# Clape_SCH.net
KiCad netlist of a schematic drawn in Altium Designer
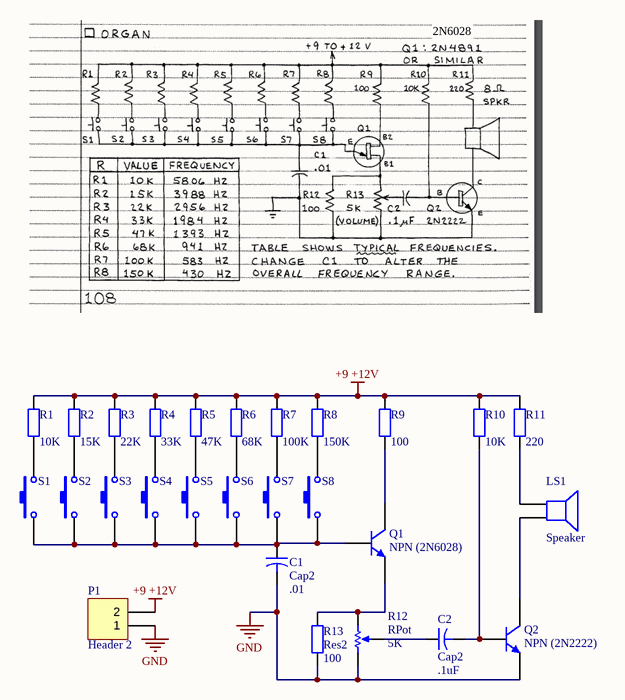
[diagram p0: Clape SCH.SchDoc]

(export (version "E")
  (design (tool "Eeschema 10.0.6"))
  (components
    (comp (ref "C1")
      (value "Cap2")
      (footprint "CAPR5-4X5")
      (description "Capacitor")
      (fields (field (name "ALTIUM_VALUE") ".01") (field (name "PUBLISHER") "Altium Limited"))
      (libsource (lib "Miscellaneous Devices") (part "Cap2"))
    )
    (comp (ref "C2")
      (value "Cap2")
      (footprint "CAPR5-4X5")
      (description "Capacitor")
      (fields (field (name "ALTIUM_VALUE") ".1uF") (field (name "PUBLISHER") "Altium Limited"))
      (libsource (lib "Miscellaneous Devices") (part "Cap2"))
    )
    (comp (ref "LS1")
      (value "Speaker")
      (footprint "PIN2")
      (description "Loudspeaker")
      (fields (field (name "PUBLISHER") "Altium Limited"))
      (libsource (lib "Miscellaneous Devices") (part "Speaker"))
    )
    (comp (ref "P1")
      (value "Header 2")
      (footprint "HDR1X2")
      (description "Header, 2-Pin")
      (fields (field (name "PUBLISHER") "Altium Limited"))
      (libsource (lib "Miscellaneous Connectors") (part "Header 2"))
    )
    (comp (ref "Q1")
      (value "NPN (2N6028)")
      (footprint "TO-226-AA")
      (description "NPN Bipolar Transistor")
      (fields (field (name "PUBLISHER") "Altium Limited"))
      (libsource (lib "Miscellaneous Devices") (part "NPN"))
    )
    (comp (ref "Q2")
      (value "NPN (2N2222)")
      (footprint "TO-226-AA")
      (description "NPN Bipolar Transistor")
      (fields (field (name "PUBLISHER") "Altium Limited"))
      (libsource (lib "Miscellaneous Devices") (part "NPN"))
    )
    (comp (ref "R1")
      (value "10K")
      (footprint "AXIAL-0.4")
      (description "Resistor")
      (fields (field (name "Comment") "Res2") (field (name "PUBLISHER") "Altium Limited"))
      (libsource (lib "Miscellaneous Devices") (part "Res2"))
    )
    (comp (ref "R2")
      (value "15K")
      (footprint "AXIAL-0.4")
      (description "Resistor")
      (fields (field (name "Comment") "Res2") (field (name "PUBLISHER") "Altium Limited"))
      (libsource (lib "Miscellaneous Devices") (part "Res2"))
    )
    (comp (ref "R3")
      (value "22K")
      (footprint "AXIAL-0.4")
      (description "Resistor")
      (fields (field (name "Comment") "Res2") (field (name "PUBLISHER") "Altium Limited"))
      (libsource (lib "Miscellaneous Devices") (part "Res2"))
    )
    (comp (ref "R4")
      (value "33K")
      (footprint "AXIAL-0.4")
      (description "Resistor")
      (fields (field (name "Comment") "Res2") (field (name "PUBLISHER") "Altium Limited"))
      (libsource (lib "Miscellaneous Devices") (part "Res2"))
    )
    (comp (ref "R5")
      (value "47K")
      (footprint "AXIAL-0.4")
      (description "Resistor")
      (fields (field (name "Comment") "Res2") (field (name "PUBLISHER") "Altium Limited"))
      (libsource (lib "Miscellaneous Devices") (part "Res2"))
    )
    (comp (ref "R6")
      (value "68K")
      (footprint "AXIAL-0.4")
      (description "Resistor")
      (fields (field (name "Comment") "Res2") (field (name "PUBLISHER") "Altium Limited"))
      (libsource (lib "Miscellaneous Devices") (part "Res2"))
    )
    (comp (ref "R7")
      (value "100K")
      (footprint "AXIAL-0.4")
      (description "Resistor")
      (fields (field (name "Comment") "Res2") (field (name "PUBLISHER") "Altium Limited"))
      (libsource (lib "Miscellaneous Devices") (part "Res2"))
    )
    (comp (ref "R8")
      (value "150K")
      (footprint "AXIAL-0.4")
      (description "Resistor")
      (fields (field (name "Comment") "Res2") (field (name "PUBLISHER") "Altium Limited"))
      (libsource (lib "Miscellaneous Devices") (part "Res2"))
    )
    (comp (ref "R9")
      (value "100")
      (footprint "AXIAL-0.4")
      (description "Resistor")
      (fields (field (name "Comment") "Res2") (field (name "PUBLISHER") "Altium Limited"))
      (libsource (lib "Miscellaneous Devices") (part "Res2"))
    )
    (comp (ref "R10")
      (value "10K")
      (footprint "AXIAL-0.4")
      (description "Resistor")
      (fields (field (name "Comment") "Res2") (field (name "PUBLISHER") "Altium Limited"))
      (libsource (lib "Miscellaneous Devices") (part "Res2"))
    )
    (comp (ref "R11")
      (value "220")
      (footprint "AXIAL-0.4")
      (description "Resistor")
      (fields (field (name "Comment") "Res2") (field (name "PUBLISHER") "Altium Limited"))
      (libsource (lib "Miscellaneous Devices") (part "Res2"))
    )
    (comp (ref "R12")
      (value "RPot")
      (footprint "VR5")
      (description "Potentiometer")
      (fields (field (name "ALTIUM_VALUE") "5K") (field (name "PUBLISHER") "Altium Limited"))
      (libsource (lib "Miscellaneous Devices") (part "RPot"))
    )
    (comp (ref "R13")
      (value "Res2")
      (footprint "AXIAL-0.4")
      (description "Resistor")
      (fields (field (name "ALTIUM_VALUE") "100") (field (name "PUBLISHER") "Altium Limited"))
      (libsource (lib "Miscellaneous Devices") (part "Res2"))
    )
    (comp (ref "S1")
      (value "SW-PB")
      (footprint "SPST-2")
      (description "Switch")
      (fields (field (name "PUBLISHER") "Altium Limited"))
      (libsource (lib "Miscellaneous Devices") (part "SW-PB"))
    )
    (comp (ref "S2")
      (value "SW-PB")
      (footprint "SPST-2")
      (description "Switch")
      (fields (field (name "PUBLISHER") "Altium Limited"))
      (libsource (lib "Miscellaneous Devices") (part "SW-PB"))
    )
    (comp (ref "S3")
      (value "SW-PB")
      (footprint "SPST-2")
      (description "Switch")
      (fields (field (name "PUBLISHER") "Altium Limited"))
      (libsource (lib "Miscellaneous Devices") (part "SW-PB"))
    )
    (comp (ref "S4")
      (value "SW-PB")
      (footprint "SPST-2")
      (description "Switch")
      (fields (field (name "PUBLISHER") "Altium Limited"))
      (libsource (lib "Miscellaneous Devices") (part "SW-PB"))
    )
    (comp (ref "S5")
      (value "SW-PB")
      (footprint "SPST-2")
      (description "Switch")
      (fields (field (name "PUBLISHER") "Altium Limited"))
      (libsource (lib "Miscellaneous Devices") (part "SW-PB"))
    )
    (comp (ref "S6")
      (value "SW-PB")
      (footprint "SPST-2")
      (description "Switch")
      (fields (field (name "PUBLISHER") "Altium Limited"))
      (libsource (lib "Miscellaneous Devices") (part "SW-PB"))
    )
    (comp (ref "S7")
      (value "SW-PB")
      (footprint "SPST-2")
      (description "Switch")
      (fields (field (name "PUBLISHER") "Altium Limited"))
      (libsource (lib "Miscellaneous Devices") (part "SW-PB"))
    )
    (comp (ref "S8")
      (value "SW-PB")
      (footprint "SPST-2")
      (description "Switch")
      (fields (field (name "PUBLISHER") "Altium Limited"))
      (libsource (lib "Miscellaneous Devices") (part "SW-PB"))
    )
  )
  (nets
    (net (code "1") (name "+9 +12V") (class "Default")
      (node (ref "P1") (pin "2") (pinfunction "2_2") (pintype "passive"))
      (node (ref "R1") (pin "2") (pinfunction "2_2") (pintype "passive"))
      (node (ref "R10") (pin "2") (pinfunction "2_2") (pintype "passive"))
      (node (ref "R11") (pin "2") (pinfunction "2_2") (pintype "passive"))
      (node (ref "R2") (pin "2") (pinfunction "2_2") (pintype "passive"))
      (node (ref "R3") (pin "2") (pinfunction "2_2") (pintype "passive"))
      (node (ref "R4") (pin "2") (pinfunction "2_2") (pintype "passive"))
      (node (ref "R5") (pin "2") (pinfunction "2_2") (pintype "passive"))
      (node (ref "R6") (pin "2") (pinfunction "2_2") (pintype "passive"))
      (node (ref "R7") (pin "2") (pinfunction "2_2") (pintype "passive"))
      (node (ref "R8") (pin "2") (pinfunction "2_2") (pintype "passive"))
      (node (ref "R9") (pin "2") (pinfunction "2_2") (pintype "passive"))
    )
    (net (code "2") (name "GND") (class "Default")
      (node (ref "C1") (pin "2") (pinfunction "2_2") (pintype "passive"))
      (node (ref "P1") (pin "1") (pinfunction "1_1") (pintype "passive"))
      (node (ref "Q2") (pin "3") (pinfunction "E_3") (pintype "passive"))
      (node (ref "R12") (pin "1") (pinfunction "TOP_1") (pintype "passive"))
      (node (ref "R13") (pin "1") (pinfunction "1_1") (pintype "passive"))
    )
    (net (code "3") (name "Net-(LS1-Pad1)") (class "Default")
      (node (ref "LS1") (pin "1") (pinfunction "1_1") (pintype "passive"))
      (node (ref "R11") (pin "1") (pinfunction "1_1") (pintype "passive"))
    )
    (net (code "4") (name "Net-(Q1-B)") (class "Default")
      (node (ref "C1") (pin "1") (pinfunction "1_1") (pintype "passive"))
      (node (ref "Q1") (pin "2") (pinfunction "B_2") (pintype "passive"))
      (node (ref "S1") (pin "1") (pinfunction "1_1") (pintype "passive"))
      (node (ref "S2") (pin "1") (pinfunction "1_1") (pintype "passive"))
      (node (ref "S3") (pin "1") (pinfunction "1_1") (pintype "passive"))
      (node (ref "S4") (pin "1") (pinfunction "1_1") (pintype "passive"))
      (node (ref "S5") (pin "1") (pinfunction "1_1") (pintype "passive"))
      (node (ref "S6") (pin "1") (pinfunction "1_1") (pintype "passive"))
      (node (ref "S7") (pin "1") (pinfunction "1_1") (pintype "passive"))
      (node (ref "S8") (pin "1") (pinfunction "1_1") (pintype "passive"))
    )
    (net (code "5") (name "Net-(Q1-C)") (class "Default")
      (node (ref "Q1") (pin "1") (pinfunction "C_1") (pintype "passive"))
      (node (ref "R9") (pin "1") (pinfunction "1_1") (pintype "passive"))
    )
    (net (code "6") (name "Net-(Q1-E)") (class "Default")
      (node (ref "Q1") (pin "3") (pinfunction "E_3") (pintype "passive"))
      (node (ref "R12") (pin "2") (pinfunction "BOT_2") (pintype "passive"))
      (node (ref "R13") (pin "2") (pinfunction "2_2") (pintype "passive"))
    )
    (net (code "7") (name "Net-(Q2-B)") (class "Default")
      (node (ref "C2") (pin "2") (pinfunction "2_2") (pintype "passive"))
      (node (ref "Q2") (pin "2") (pinfunction "B_2") (pintype "passive"))
      (node (ref "R10") (pin "1") (pinfunction "1_1") (pintype "passive"))
    )
    (net (code "8") (name "Net-(Q2-C)") (class "Default")
      (node (ref "LS1") (pin "2") (pinfunction "2_2") (pintype "passive"))
      (node (ref "Q2") (pin "1") (pinfunction "C_1") (pintype "passive"))
    )
    (net (code "9") (name "Net-(R1-Pad1)") (class "Default")
      (node (ref "R1") (pin "1") (pinfunction "1_1") (pintype "passive"))
      (node (ref "S1") (pin "2") (pinfunction "2_2") (pintype "passive"))
    )
    (net (code "10") (name "Net-(R2-Pad1)") (class "Default")
      (node (ref "R2") (pin "1") (pinfunction "1_1") (pintype "passive"))
      (node (ref "S2") (pin "2") (pinfunction "2_2") (pintype "passive"))
    )
    (net (code "11") (name "Net-(R3-Pad1)") (class "Default")
      (node (ref "R3") (pin "1") (pinfunction "1_1") (pintype "passive"))
      (node (ref "S3") (pin "2") (pinfunction "2_2") (pintype "passive"))
    )
    (net (code "12") (name "Net-(R4-Pad1)") (class "Default")
      (node (ref "R4") (pin "1") (pinfunction "1_1") (pintype "passive"))
      (node (ref "S4") (pin "2") (pinfunction "2_2") (pintype "passive"))
    )
    (net (code "13") (name "Net-(R5-Pad1)") (class "Default")
      (node (ref "R5") (pin "1") (pinfunction "1_1") (pintype "passive"))
      (node (ref "S5") (pin "2") (pinfunction "2_2") (pintype "passive"))
    )
    (net (code "14") (name "Net-(R6-Pad1)") (class "Default")
      (node (ref "R6") (pin "1") (pinfunction "1_1") (pintype "passive"))
      (node (ref "S6") (pin "2") (pinfunction "2_2") (pintype "passive"))
    )
    (net (code "15") (name "Net-(R7-Pad1)") (class "Default")
      (node (ref "R7") (pin "1") (pinfunction "1_1") (pintype "passive"))
      (node (ref "S7") (pin "2") (pinfunction "2_2") (pintype "passive"))
    )
    (net (code "16") (name "Net-(R8-Pad1)") (class "Default")
      (node (ref "R8") (pin "1") (pinfunction "1_1") (pintype "passive"))
      (node (ref "S8") (pin "2") (pinfunction "2_2") (pintype "passive"))
    )
    (net (code "17") (name "Net-(R12-TAP)") (class "Default")
      (node (ref "C2") (pin "1") (pinfunction "1_1") (pintype "passive"))
      (node (ref "R12") (pin "3") (pinfunction "TAP_3") (pintype "passive"))
    )
  )
)
